# Atmega_programmer_cct_diagram.net
KiCad netlist of a schematic drawn in EAGLE
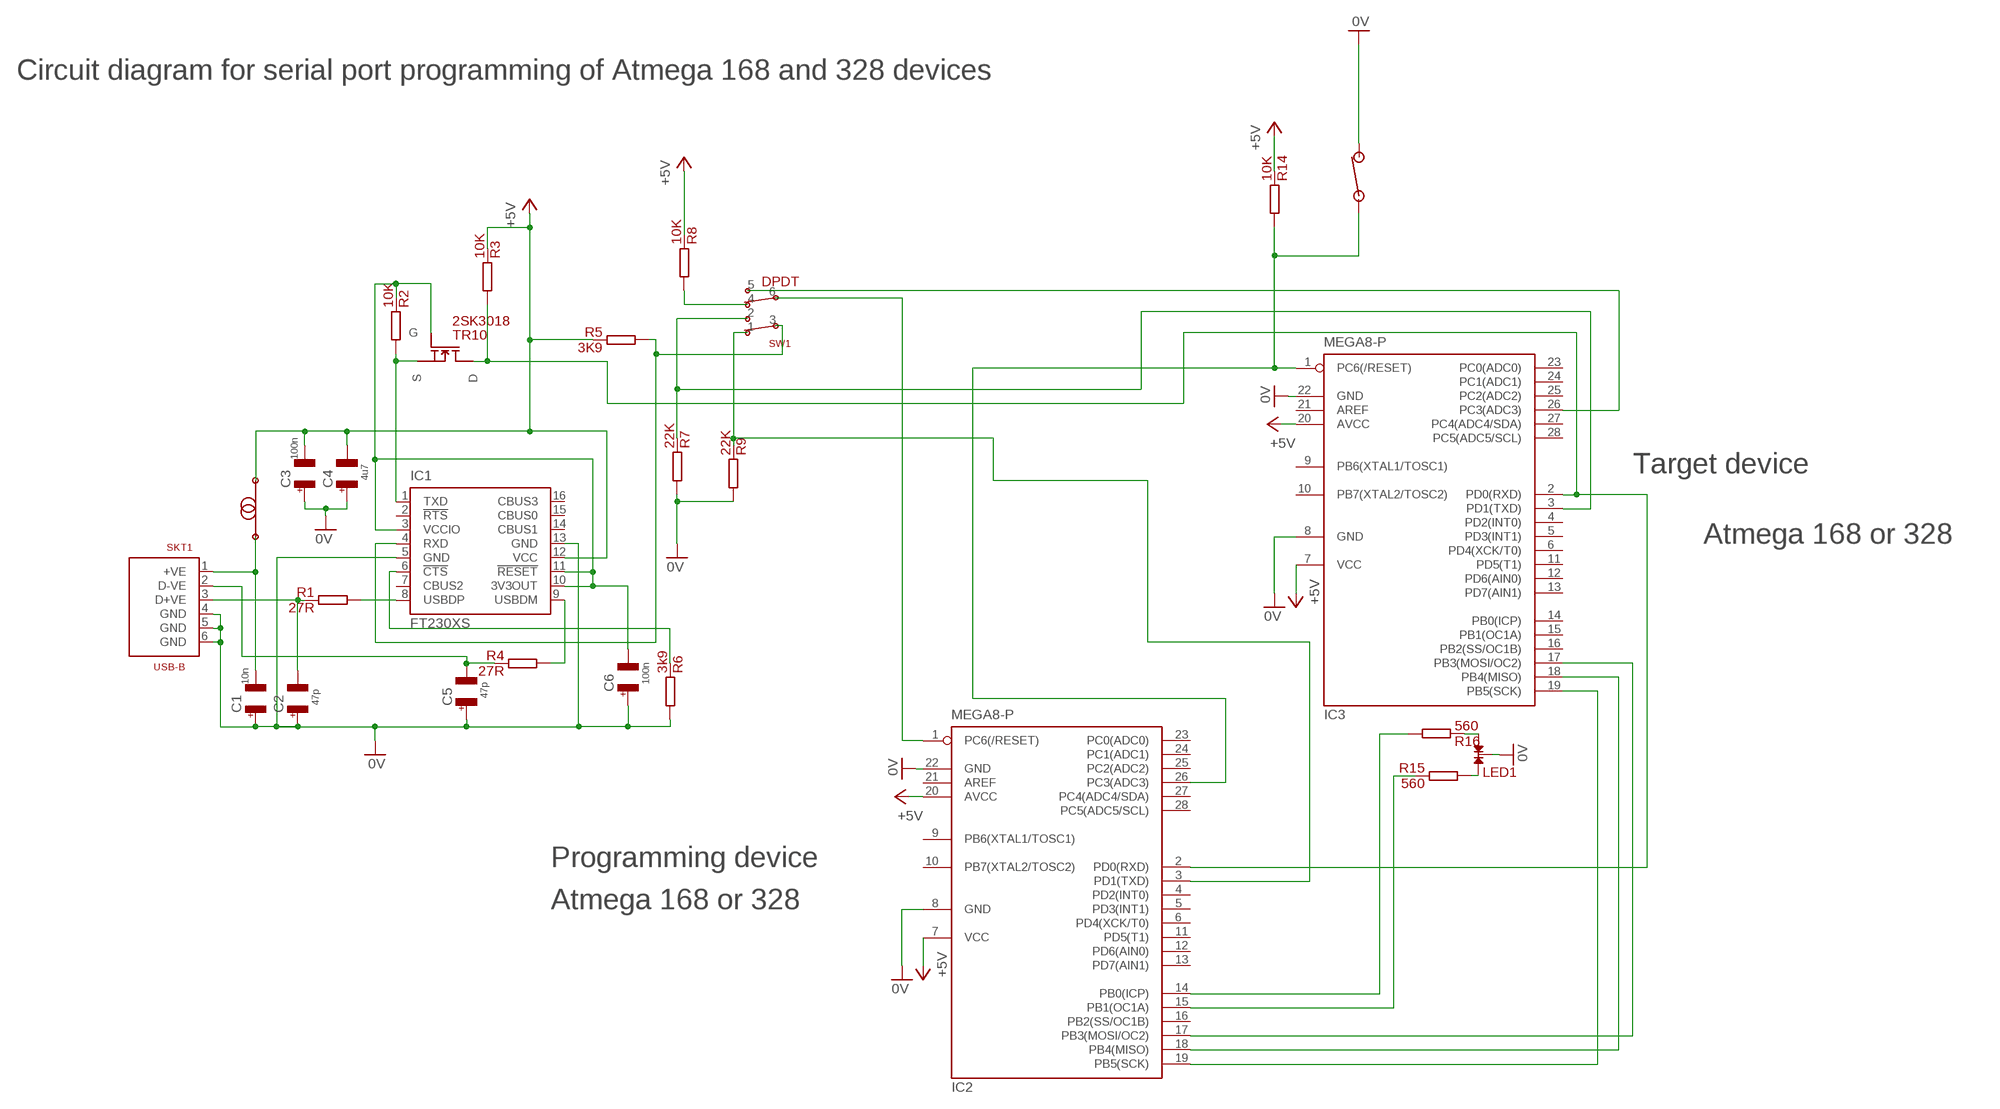
[diagram p0: schematic, sheet 1]

(export (version "E")
  (design (tool "Eeschema 10.0.6"))
  (components
    (comp (ref "C1")
      (value "10n")
      (footprint "eagle-import:1206")
      (libsource (lib "eagle-import") (part "1206C"))
    )
    (comp (ref "C2")
      (value "47p")
      (footprint "eagle-import:1206")
      (libsource (lib "eagle-import") (part "1206C"))
    )
    (comp (ref "C3")
      (value "100n")
      (footprint "eagle-import:1206")
      (libsource (lib "eagle-import") (part "1206C"))
    )
    (comp (ref "C4")
      (value "4u7")
      (footprint "eagle-import:1206")
      (libsource (lib "eagle-import") (part "1206C"))
    )
    (comp (ref "C5")
      (value "47p")
      (footprint "eagle-import:1206")
      (libsource (lib "eagle-import") (part "1206C"))
    )
    (comp (ref "C6")
      (value "100n")
      (footprint "eagle-import:1206")
      (libsource (lib "eagle-import") (part "1206C"))
    )
    (comp (ref "IC1")
      (value "FT230XS")
      (footprint "eagle-import:SSOP16")
      (libsource (lib "eagle-import") (part "FT230XS"))
    )
    (comp (ref "IC2")
      (value "MEGA8-P")
      (footprint "eagle-import:DIL28-3")
      (libsource (lib "eagle-import") (part "MEGA8-P"))
    )
    (comp (ref "IC3")
      (value "MEGA8-P")
      (footprint "eagle-import:DIL28-3")
      (libsource (lib "eagle-import") (part "MEGA8-P"))
    )
    (comp (ref "L1")
      (value "CHOKE")
      (footprint "eagle-import:1206")
      (libsource (lib "eagle-import") (part "CHOKE"))
    )
    (comp (ref "LED1")
      (value "LED")
      (footprint "eagle-import:CA_DUAL_LED")
      (libsource (lib "eagle-import") (part "LED"))
    )
    (comp (ref "R1")
      (value "27R")
      (footprint "eagle-import:1206")
      (libsource (lib "eagle-import") (part "1206R"))
    )
    (comp (ref "R2")
      (value "10K")
      (footprint "eagle-import:1206")
      (libsource (lib "eagle-import") (part "1206R"))
    )
    (comp (ref "R3")
      (value "10K")
      (footprint "eagle-import:1206")
      (libsource (lib "eagle-import") (part "1206R"))
    )
    (comp (ref "R4")
      (value "27R")
      (footprint "eagle-import:1206")
      (libsource (lib "eagle-import") (part "1206R"))
    )
    (comp (ref "R5")
      (value "3K9")
      (footprint "eagle-import:1206")
      (libsource (lib "eagle-import") (part "1206R"))
    )
    (comp (ref "R6")
      (value "3k9")
      (footprint "eagle-import:1206")
      (libsource (lib "eagle-import") (part "1206R"))
    )
    (comp (ref "R7")
      (value "22K")
      (footprint "eagle-import:1206")
      (libsource (lib "eagle-import") (part "1206R"))
    )
    (comp (ref "R8")
      (value "10K")
      (footprint "eagle-import:1206")
      (libsource (lib "eagle-import") (part "1206R"))
    )
    (comp (ref "R9")
      (value "22K")
      (footprint "eagle-import:1206")
      (libsource (lib "eagle-import") (part "1206R"))
    )
    (comp (ref "R14")
      (value "10K")
      (footprint "eagle-import:1206")
      (libsource (lib "eagle-import") (part "1206R"))
    )
    (comp (ref "R15")
      (value "560")
      (footprint "eagle-import:1206")
      (libsource (lib "eagle-import") (part "1206R"))
    )
    (comp (ref "R16")
      (value "560")
      (footprint "eagle-import:1206")
      (libsource (lib "eagle-import") (part "1206R"))
    )
    (comp (ref "SKT1")
      (value "USB-B")
      (footprint "eagle-import:USB-B")
      (libsource (lib "eagle-import") (part "USB-B"))
    )
    (comp (ref "SW1")
      (value "DPDT")
      (footprint "eagle-import:DPDT_SWITCH")
      (libsource (lib "eagle-import") (part "DPDT"))
    )
    (comp (ref "SW2")
      (value "NO_SW")
      (footprint "eagle-import:SM_NO_PUSH_BUTTON")
      (libsource (lib "eagle-import") (part "NO_SW"))
    )
    (comp (ref "TR10")
      (value "2SK3018")
      (footprint "eagle-import:2SK3018")
      (libsource (lib "eagle-import") (part "2SK3018"))
    )
  )
  (nets
    (net (code "1") (name "+5V") (class "Default")
      (node (ref "C3") (pin "P$2") (pinfunction "2_P$2") (pintype "bidirectional"))
      (node (ref "C4") (pin "P$2") (pinfunction "2_P$2") (pintype "bidirectional"))
      (node (ref "IC1") (pin "12") (pinfunction "VCC_12") (pintype "power_in"))
      (node (ref "IC2") (pin "20") (pinfunction "AVCC_20") (pintype "power_in"))
      (node (ref "IC2") (pin "7") (pinfunction "VCC_7") (pintype "power_in"))
      (node (ref "IC3") (pin "20") (pinfunction "AVCC_20") (pintype "power_in"))
      (node (ref "IC3") (pin "7") (pinfunction "VCC_7") (pintype "power_in"))
      (node (ref "L1") (pin "P$2") (pinfunction "2_P$2") (pintype "bidirectional"))
      (node (ref "R14") (pin "P$2") (pinfunction "P$2_P$2") (pintype "bidirectional"))
      (node (ref "R3") (pin "P$2") (pinfunction "P$2_P$2") (pintype "bidirectional"))
      (node (ref "R5") (pin "P$2") (pinfunction "P$2_P$2") (pintype "bidirectional"))
      (node (ref "R8") (pin "P$2") (pinfunction "P$2_P$2") (pintype "bidirectional"))
    )
    (net (code "2") (name "0V") (class "Default")
      (node (ref "C1") (pin "P$1") (pinfunction "1_P$1") (pintype "bidirectional"))
      (node (ref "C2") (pin "P$1") (pinfunction "1_P$1") (pintype "bidirectional"))
      (node (ref "C3") (pin "P$1") (pinfunction "1_P$1") (pintype "bidirectional"))
      (node (ref "C4") (pin "P$1") (pinfunction "1_P$1") (pintype "bidirectional"))
      (node (ref "C5") (pin "P$1") (pinfunction "1_P$1") (pintype "bidirectional"))
      (node (ref "C6") (pin "P$1") (pinfunction "1_P$1") (pintype "bidirectional"))
      (node (ref "IC1") (pin "13") (pinfunction "GND_13") (pintype "power_in"))
      (node (ref "IC1") (pin "5") (pinfunction "GND_5") (pintype "power_in"))
      (node (ref "IC2") (pin "22") (pinfunction "GND_22") (pintype "power_in"))
      (node (ref "IC2") (pin "8") (pinfunction "GND_8") (pintype "power_in"))
      (node (ref "IC3") (pin "22") (pinfunction "GND_22") (pintype "power_in"))
      (node (ref "IC3") (pin "8") (pinfunction "GND_8") (pintype "power_in"))
      (node (ref "LED1") (pin "2") (pinfunction "2_2") (pintype "bidirectional"))
      (node (ref "R6") (pin "P$1") (pinfunction "P$1_P$1") (pintype "bidirectional"))
      (node (ref "R7") (pin "P$1") (pinfunction "P$1_P$1") (pintype "bidirectional"))
      (node (ref "R9") (pin "P$1") (pinfunction "P$1_P$1") (pintype "bidirectional"))
      (node (ref "SKT1") (pin "4") (pinfunction "GND_4") (pintype "bidirectional"))
      (node (ref "SKT1") (pin "5") (pinfunction "GND_5") (pintype "bidirectional"))
      (node (ref "SKT1") (pin "6") (pinfunction "GND_6") (pintype "bidirectional"))
      (node (ref "SW2") (pin "P$2") (pinfunction "2_P$2") (pintype "bidirectional"))
    )
    (net (code "3") (name "Net-(C1-2)") (class "Default")
      (node (ref "C1") (pin "P$2") (pinfunction "2_P$2") (pintype "bidirectional"))
      (node (ref "L1") (pin "P$1") (pinfunction "1_P$1") (pintype "bidirectional"))
      (node (ref "SKT1") (pin "1") (pinfunction "+VE_1") (pintype "bidirectional"))
    )
    (net (code "4") (name "Net-(C2-2)") (class "Default")
      (node (ref "C2") (pin "P$2") (pinfunction "2_P$2") (pintype "bidirectional"))
      (node (ref "R1") (pin "P$2") (pinfunction "P$2_P$2") (pintype "bidirectional"))
      (node (ref "SKT1") (pin "3") (pinfunction "D+VE_3") (pintype "bidirectional"))
    )
    (net (code "5") (name "Net-(C5-2)") (class "Default")
      (node (ref "C5") (pin "P$2") (pinfunction "2_P$2") (pintype "bidirectional"))
      (node (ref "R4") (pin "P$2") (pinfunction "P$2_P$2") (pintype "bidirectional"))
      (node (ref "SKT1") (pin "2") (pinfunction "D-VE_2") (pintype "bidirectional"))
    )
    (net (code "6") (name "Net-(C6-2)") (class "Default")
      (node (ref "C6") (pin "P$2") (pinfunction "2_P$2") (pintype "bidirectional"))
      (node (ref "IC1") (pin "10") (pinfunction "3V3OUT_10") (pintype "output"))
      (node (ref "IC1") (pin "11") (pinfunction "~{RESET}_11") (pintype "input"))
      (node (ref "IC1") (pin "3") (pinfunction "VCCIO_3") (pintype "power_in"))
      (node (ref "R2") (pin "P$2") (pinfunction "P$2_P$2") (pintype "bidirectional"))
      (node (ref "TR10") (pin "2") (pinfunction "G_2") (pintype "bidirectional"))
    )
    (net (code "7") (name "Net-(IC1-RXD)") (class "Default")
      (node (ref "IC1") (pin "4") (pinfunction "RXD_4") (pintype "input"))
      (node (ref "R5") (pin "P$1") (pinfunction "P$1_P$1") (pintype "bidirectional"))
      (node (ref "SW1") (pin "3") (pinfunction "3_3") (pintype "bidirectional"))
    )
    (net (code "8") (name "Net-(IC1-TXD)") (class "Default")
      (node (ref "IC1") (pin "1") (pinfunction "TXD_1") (pintype "output"))
      (node (ref "R2") (pin "P$1") (pinfunction "P$1_P$1") (pintype "bidirectional"))
      (node (ref "TR10") (pin "1") (pinfunction "S_1") (pintype "bidirectional"))
    )
    (net (code "9") (name "Net-(IC1-USBDM)") (class "Default")
      (node (ref "IC1") (pin "9") (pinfunction "USBDM_9") (pintype "input"))
      (node (ref "R4") (pin "P$1") (pinfunction "P$1_P$1") (pintype "bidirectional"))
    )
    (net (code "10") (name "Net-(IC1-USBDP)") (class "Default")
      (node (ref "IC1") (pin "8") (pinfunction "USBDP_8") (pintype "input"))
      (node (ref "R1") (pin "P$1") (pinfunction "P$1_P$1") (pintype "bidirectional"))
    )
    (net (code "11") (name "Net-(IC1-~{CTS})") (class "Default")
      (node (ref "IC1") (pin "6") (pinfunction "~{CTS}_6") (pintype "input"))
      (node (ref "R6") (pin "P$2") (pinfunction "P$2_P$2") (pintype "bidirectional"))
    )
    (net (code "12") (name "Net-(IC2-PB0(ICP))") (class "Default")
      (node (ref "IC2") (pin "14") (pinfunction "PB0(ICP)_14") (pintype "bidirectional"))
      (node (ref "R16") (pin "P$1") (pinfunction "P$1_P$1") (pintype "bidirectional"))
    )
    (net (code "13") (name "Net-(IC2-PB1(OC1A))") (class "Default")
      (node (ref "IC2") (pin "15") (pinfunction "PB1(OC1A)_15") (pintype "bidirectional"))
      (node (ref "R15") (pin "P$2") (pinfunction "P$2_P$2") (pintype "bidirectional"))
    )
    (net (code "14") (name "Net-(IC2-PB3(MOSI{slash}OC2))") (class "Default")
      (node (ref "IC2") (pin "17") (pinfunction "PB3(MOSI/OC2)_17") (pintype "bidirectional"))
      (node (ref "IC3") (pin "17") (pinfunction "PB3(MOSI/OC2)_17") (pintype "bidirectional"))
    )
    (net (code "15") (name "Net-(IC2-PB4(MISO))") (class "Default")
      (node (ref "IC2") (pin "18") (pinfunction "PB4(MISO)_18") (pintype "bidirectional"))
      (node (ref "IC3") (pin "18") (pinfunction "PB4(MISO)_18") (pintype "bidirectional"))
    )
    (net (code "16") (name "Net-(IC2-PB5(SCK))") (class "Default")
      (node (ref "IC2") (pin "19") (pinfunction "PB5(SCK)_19") (pintype "bidirectional"))
      (node (ref "IC3") (pin "19") (pinfunction "PB5(SCK)_19") (pintype "bidirectional"))
    )
    (net (code "17") (name "Net-(IC2-PC3(ADC3))") (class "Default")
      (node (ref "IC2") (pin "26") (pinfunction "PC3(ADC3)_26") (pintype "bidirectional"))
      (node (ref "IC3") (pin "1") (pinfunction "PC6(/RESET)_1") (pintype "bidirectional"))
      (node (ref "R14") (pin "P$1") (pinfunction "P$1_P$1") (pintype "bidirectional"))
      (node (ref "SW2") (pin "P$1") (pinfunction "1_P$1") (pintype "bidirectional"))
    )
    (net (code "18") (name "Net-(IC2-PC6({slash}RESET))") (class "Default")
      (node (ref "IC2") (pin "1") (pinfunction "PC6(/RESET)_1") (pintype "bidirectional"))
      (node (ref "SW1") (pin "6") (pinfunction "6_6") (pintype "bidirectional"))
    )
    (net (code "19") (name "Net-(IC2-PD0(RXD))") (class "Default")
      (node (ref "IC2") (pin "2") (pinfunction "PD0(RXD)_2") (pintype "bidirectional"))
      (node (ref "IC3") (pin "2") (pinfunction "PD0(RXD)_2") (pintype "bidirectional"))
      (node (ref "R3") (pin "P$1") (pinfunction "P$1_P$1") (pintype "bidirectional"))
      (node (ref "TR10") (pin "3") (pinfunction "D_3") (pintype "bidirectional"))
    )
    (net (code "20") (name "Net-(IC2-PD1(TXD))") (class "Default")
      (node (ref "IC2") (pin "3") (pinfunction "PD1(TXD)_3") (pintype "bidirectional"))
      (node (ref "R9") (pin "P$2") (pinfunction "P$2_P$2") (pintype "bidirectional"))
      (node (ref "SW1") (pin "1") (pinfunction "1_1") (pintype "bidirectional"))
    )
    (net (code "21") (name "Net-(IC3-PC3(ADC3))") (class "Default")
      (node (ref "IC3") (pin "26") (pinfunction "PC3(ADC3)_26") (pintype "bidirectional"))
      (node (ref "SW1") (pin "5") (pinfunction "5_5") (pintype "bidirectional"))
    )
    (net (code "22") (name "Net-(IC3-PD1(TXD))") (class "Default")
      (node (ref "IC3") (pin "3") (pinfunction "PD1(TXD)_3") (pintype "bidirectional"))
      (node (ref "R7") (pin "P$2") (pinfunction "P$2_P$2") (pintype "bidirectional"))
      (node (ref "SW1") (pin "2") (pinfunction "2_2") (pintype "bidirectional"))
    )
    (net (code "23") (name "Net-(LED1-Pad1)") (class "Default")
      (node (ref "LED1") (pin "1") (pinfunction "1_1") (pintype "bidirectional"))
      (node (ref "R15") (pin "P$1") (pinfunction "P$1_P$1") (pintype "bidirectional"))
    )
    (net (code "24") (name "Net-(LED1-Pad3)") (class "Default")
      (node (ref "LED1") (pin "3") (pinfunction "3_3") (pintype "bidirectional"))
      (node (ref "R16") (pin "P$2") (pinfunction "P$2_P$2") (pintype "bidirectional"))
    )
    (net (code "25") (name "Net-(R8-PadP$1)") (class "Default")
      (node (ref "R8") (pin "P$1") (pinfunction "P$1_P$1") (pintype "bidirectional"))
      (node (ref "SW1") (pin "4") (pinfunction "4_4") (pintype "bidirectional"))
    )
    (net (code "26") (name "unconnected-(IC1-CBUS0-Pad15)") (class "Default")
      (node (ref "IC1") (pin "15") (pinfunction "CBUS0_15") (pintype "bidirectional"))
    )
    (net (code "27") (name "unconnected-(IC1-CBUS1-Pad14)") (class "Default")
      (node (ref "IC1") (pin "14") (pinfunction "CBUS1_14") (pintype "bidirectional"))
    )
    (net (code "28") (name "unconnected-(IC1-CBUS2-Pad7)") (class "Default")
      (node (ref "IC1") (pin "7") (pinfunction "CBUS2_7") (pintype "bidirectional"))
    )
    (net (code "29") (name "unconnected-(IC1-CBUS3-Pad16)") (class "Default")
      (node (ref "IC1") (pin "16") (pinfunction "CBUS3_16") (pintype "bidirectional"))
    )
    (net (code "30") (name "unconnected-(IC1-~{RTS}-Pad2)") (class "Default")
      (node (ref "IC1") (pin "2") (pinfunction "~{RTS}_2") (pintype "output"))
    )
    (net (code "31") (name "unconnected-(IC2-AREF-Pad21)") (class "Default")
      (node (ref "IC2") (pin "21") (pinfunction "AREF_21") (pintype "passive"))
    )
    (net (code "32") (name "unconnected-(IC2-PB2(SS{slash}OC1B)-Pad16)") (class "Default")
      (node (ref "IC2") (pin "16") (pinfunction "PB2(SS/OC1B)_16") (pintype "bidirectional"))
    )
    (net (code "33") (name "unconnected-(IC2-PB6(XTAL1{slash}TOSC1)-Pad9)") (class "Default")
      (node (ref "IC2") (pin "9") (pinfunction "PB6(XTAL1/TOSC1)_9") (pintype "bidirectional"))
    )
    (net (code "34") (name "unconnected-(IC2-PB7(XTAL2{slash}TOSC2)-Pad10)") (class "Default")
      (node (ref "IC2") (pin "10") (pinfunction "PB7(XTAL2/TOSC2)_10") (pintype "bidirectional"))
    )
    (net (code "35") (name "unconnected-(IC2-PC0(ADC0)-Pad23)") (class "Default")
      (node (ref "IC2") (pin "23") (pinfunction "PC0(ADC0)_23") (pintype "bidirectional"))
    )
    (net (code "36") (name "unconnected-(IC2-PC1(ADC1)-Pad24)") (class "Default")
      (node (ref "IC2") (pin "24") (pinfunction "PC1(ADC1)_24") (pintype "bidirectional"))
    )
    (net (code "37") (name "unconnected-(IC2-PC2(ADC2)-Pad25)") (class "Default")
      (node (ref "IC2") (pin "25") (pinfunction "PC2(ADC2)_25") (pintype "bidirectional"))
    )
    (net (code "38") (name "unconnected-(IC2-PC4(ADC4{slash}SDA)-Pad27)") (class "Default")
      (node (ref "IC2") (pin "27") (pinfunction "PC4(ADC4/SDA)_27") (pintype "bidirectional"))
    )
    (net (code "39") (name "unconnected-(IC2-PC5(ADC5{slash}SCL)-Pad28)") (class "Default")
      (node (ref "IC2") (pin "28") (pinfunction "PC5(ADC5/SCL)_28") (pintype "bidirectional"))
    )
    (net (code "40") (name "unconnected-(IC2-PD2(INT0)-Pad4)") (class "Default")
      (node (ref "IC2") (pin "4") (pinfunction "PD2(INT0)_4") (pintype "bidirectional"))
    )
    (net (code "41") (name "unconnected-(IC2-PD3(INT1)-Pad5)") (class "Default")
      (node (ref "IC2") (pin "5") (pinfunction "PD3(INT1)_5") (pintype "bidirectional"))
    )
    (net (code "42") (name "unconnected-(IC2-PD4(XCK{slash}T0)-Pad6)") (class "Default")
      (node (ref "IC2") (pin "6") (pinfunction "PD4(XCK/T0)_6") (pintype "bidirectional"))
    )
    (net (code "43") (name "unconnected-(IC2-PD5(T1)-Pad11)") (class "Default")
      (node (ref "IC2") (pin "11") (pinfunction "PD5(T1)_11") (pintype "bidirectional"))
    )
    (net (code "44") (name "unconnected-(IC2-PD6(AIN0)-Pad12)") (class "Default")
      (node (ref "IC2") (pin "12") (pinfunction "PD6(AIN0)_12") (pintype "bidirectional"))
    )
    (net (code "45") (name "unconnected-(IC2-PD7(AIN1)-Pad13)") (class "Default")
      (node (ref "IC2") (pin "13") (pinfunction "PD7(AIN1)_13") (pintype "bidirectional"))
    )
    (net (code "46") (name "unconnected-(IC3-AREF-Pad21)") (class "Default")
      (node (ref "IC3") (pin "21") (pinfunction "AREF_21") (pintype "passive"))
    )
    (net (code "47") (name "unconnected-(IC3-PB0(ICP)-Pad14)") (class "Default")
      (node (ref "IC3") (pin "14") (pinfunction "PB0(ICP)_14") (pintype "bidirectional"))
    )
    (net (code "48") (name "unconnected-(IC3-PB1(OC1A)-Pad15)") (class "Default")
      (node (ref "IC3") (pin "15") (pinfunction "PB1(OC1A)_15") (pintype "bidirectional"))
    )
    (net (code "49") (name "unconnected-(IC3-PB2(SS{slash}OC1B)-Pad16)") (class "Default")
      (node (ref "IC3") (pin "16") (pinfunction "PB2(SS/OC1B)_16") (pintype "bidirectional"))
    )
    (net (code "50") (name "unconnected-(IC3-PB6(XTAL1{slash}TOSC1)-Pad9)") (class "Default")
      (node (ref "IC3") (pin "9") (pinfunction "PB6(XTAL1/TOSC1)_9") (pintype "bidirectional"))
    )
    (net (code "51") (name "unconnected-(IC3-PB7(XTAL2{slash}TOSC2)-Pad10)") (class "Default")
      (node (ref "IC3") (pin "10") (pinfunction "PB7(XTAL2/TOSC2)_10") (pintype "bidirectional"))
    )
    (net (code "52") (name "unconnected-(IC3-PC0(ADC0)-Pad23)") (class "Default")
      (node (ref "IC3") (pin "23") (pinfunction "PC0(ADC0)_23") (pintype "bidirectional"))
    )
    (net (code "53") (name "unconnected-(IC3-PC1(ADC1)-Pad24)") (class "Default")
      (node (ref "IC3") (pin "24") (pinfunction "PC1(ADC1)_24") (pintype "bidirectional"))
    )
    (net (code "54") (name "unconnected-(IC3-PC2(ADC2)-Pad25)") (class "Default")
      (node (ref "IC3") (pin "25") (pinfunction "PC2(ADC2)_25") (pintype "bidirectional"))
    )
    (net (code "55") (name "unconnected-(IC3-PC4(ADC4{slash}SDA)-Pad27)") (class "Default")
      (node (ref "IC3") (pin "27") (pinfunction "PC4(ADC4/SDA)_27") (pintype "bidirectional"))
    )
    (net (code "56") (name "unconnected-(IC3-PC5(ADC5{slash}SCL)-Pad28)") (class "Default")
      (node (ref "IC3") (pin "28") (pinfunction "PC5(ADC5/SCL)_28") (pintype "bidirectional"))
    )
    (net (code "57") (name "unconnected-(IC3-PD2(INT0)-Pad4)") (class "Default")
      (node (ref "IC3") (pin "4") (pinfunction "PD2(INT0)_4") (pintype "bidirectional"))
    )
    (net (code "58") (name "unconnected-(IC3-PD3(INT1)-Pad5)") (class "Default")
      (node (ref "IC3") (pin "5") (pinfunction "PD3(INT1)_5") (pintype "bidirectional"))
    )
    (net (code "59") (name "unconnected-(IC3-PD4(XCK{slash}T0)-Pad6)") (class "Default")
      (node (ref "IC3") (pin "6") (pinfunction "PD4(XCK/T0)_6") (pintype "bidirectional"))
    )
    (net (code "60") (name "unconnected-(IC3-PD5(T1)-Pad11)") (class "Default")
      (node (ref "IC3") (pin "11") (pinfunction "PD5(T1)_11") (pintype "bidirectional"))
    )
    (net (code "61") (name "unconnected-(IC3-PD6(AIN0)-Pad12)") (class "Default")
      (node (ref "IC3") (pin "12") (pinfunction "PD6(AIN0)_12") (pintype "bidirectional"))
    )
    (net (code "62") (name "unconnected-(IC3-PD7(AIN1)-Pad13)") (class "Default")
      (node (ref "IC3") (pin "13") (pinfunction "PD7(AIN1)_13") (pintype "bidirectional"))
    )
  )
)
